# BatteryStepDownHV.net
KiCad netlist of a schematic drawn in Altium Designer
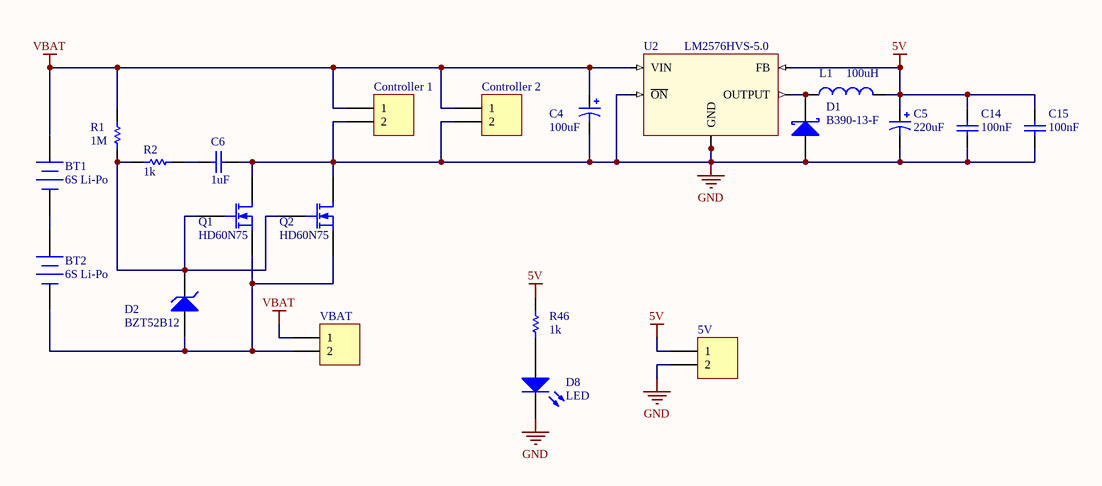
[diagram p0: BatteryStepDownHV.SchDoc]

(export (version "E")
  (design (tool "Eeschema 10.0.6"))
  (components
    (comp (ref "5V")
      (value "Header 2")
      (footprint "HDR1X2")
      (description "Header, 2-Pin")
      (fields (field (name "PUBLISHER") "Altium Limited"))
      (libsource (lib "Miscellaneous Connectors") (part "Header 2"))
    )
    (comp (ref "BT1")
      (value "6S Li-Po")
      (footprint "Wire Terminals")
      (description "Multicell Battery")
      (fields (field (name "PUBLISHER") "Altium Limited"))
      (libsource (lib "sumo") (part "Battery"))
    )
    (comp (ref "BT2")
      (value "6S Li-Po")
      (footprint "Wire Terminals")
      (description "Multicell Battery")
      (fields (field (name "PUBLISHER") "Altium Limited"))
      (libsource (lib "sumo") (part "Battery"))
    )
    (comp (ref "C4")
      (value "100uF")
      (footprint "10x10.5")
      (description "Polarized Capacitor (Radial)")
      (fields (field (name "Comment") "Cap Pol1") (field (name "PUBLISHER") "Altium Limited"))
      (libsource (lib "Miscellaneous Devices") (part "Cap Pol1"))
    )
    (comp (ref "C5")
      (value "220uF")
      (footprint "6.3X5.4")
      (description "Polarized Capacitor (Radial)")
      (fields (field (name "Comment") "Cap Pol1") (field (name "PUBLISHER") "Altium Limited"))
      (libsource (lib "Miscellaneous Devices") (part "Cap Pol1"))
    )
    (comp (ref "C6")
      (value "1uF")
      (footprint "6-0805_M")
      (description "Capacitor")
      (fields (field (name "Comment") "Cap") (field (name "PUBLISHER") "Altium Limited"))
      (libsource (lib "Miscellaneous Devices") (part "Cap"))
    )
    (comp (ref "C14")
      (value "100nF")
      (footprint "J1-0603")
      (description "Capacitor")
      (fields (field (name "Comment") "Cap") (field (name "PUBLISHER") "Altium Limited"))
      (libsource (lib "Miscellaneous Devices") (part "Cap"))
    )
    (comp (ref "C15")
      (value "100nF")
      (footprint "J1-0603")
      (description "Capacitor")
      (fields (field (name "Comment") "Cap") (field (name "PUBLISHER") "Altium Limited"))
      (libsource (lib "Miscellaneous Devices") (part "Cap"))
    )
    (comp (ref "Controller 1")
      (value "Header 2")
      (footprint "Wire Terminals")
      (description "Header, 2-Pin")
      (fields (field (name "PUBLISHER") "Altium Limited"))
      (libsource (lib "Miscellaneous Connectors") (part "Header 2"))
    )
    (comp (ref "Controller 2")
      (value "Header 2")
      (footprint "Wire Terminals")
      (description "Header, 2-Pin")
      (fields (field (name "PUBLISHER") "Altium Limited"))
      (libsource (lib "Miscellaneous Connectors") (part "Header 2"))
    )
    (comp (ref "D1")
      (value "B390-13-F")
      (footprint "B390")
      (description "Schottky Diode")
      (fields (field (name "PUBLISHER") "Altium Limited"))
      (libsource (lib "Miscellaneous Devices") (part "D Schottky"))
    )
    (comp (ref "D2")
      (value "BZT52B12")
      (footprint "SOD-123")
      (description "Zener Diode")
      (fields (field (name "PUBLISHER") "Altium Limited"))
      (libsource (lib "Miscellaneous Devices") (part "D Zener"))
    )
    (comp (ref "D8")
      (value "LED")
      (footprint "J1-0603 LED")
      (fields (field (name "PUBLISHER") "Altium Limited"))
      (libsource (lib "sumo") (part "LED"))
    )
    (comp (ref "L1")
      (value "100uH")
      (footprint "SLF12575")
      (description "Inductor")
      (fields (field (name "PUBLISHER") "Altium Limited"))
      (libsource (lib "Miscellaneous Devices") (part "Inductor"))
    )
    (comp (ref "Q1")
      (value "HD60N75")
      (footprint "TO-252")
      (description "N-Channel MOSFET 75V/60A")
      (fields (field (name "PUBLISHER") "Altium Limited"))
      (libsource (lib "sumo") (part "HD60N75"))
    )
    (comp (ref "Q2")
      (value "HD60N75")
      (footprint "TO-252")
      (description "N-Channel MOSFET 75V/60A")
      (fields (field (name "PUBLISHER") "Altium Limited"))
      (libsource (lib "sumo") (part "HD60N75"))
    )
    (comp (ref "R1")
      (value "1M")
      (footprint "J1-0603")
      (description "Resistor")
      (fields (field (name "Comment") "Res1") (field (name "PUBLISHER") "Altium Limited"))
      (libsource (lib "Miscellaneous Devices") (part "Res1"))
    )
    (comp (ref "R2")
      (value "1k")
      (footprint "J1-0603")
      (description "Resistor")
      (fields (field (name "Comment") "Res1") (field (name "PUBLISHER") "Altium Limited"))
      (libsource (lib "Miscellaneous Devices") (part "Res1"))
    )
    (comp (ref "R46")
      (value "1k")
      (footprint "J1-0603")
      (description "Resistor")
      (fields (field (name "Comment") "Res1") (field (name "PUBLISHER") "Altium Limited"))
      (libsource (lib "Miscellaneous Devices") (part "Res1"))
    )
    (comp (ref "U2")
      (value "LM2576HVS-5.0")
      (footprint "KTT0005B")
      (libsource (lib "sumo") (part "LM2576/HV"))
    )
    (comp (ref "VBAT")
      (value "Header 2")
      (footprint "HDR1X2")
      (description "Header, 2-Pin")
      (fields (field (name "PUBLISHER") "Altium Limited"))
      (libsource (lib "Miscellaneous Connectors") (part "Header 2"))
    )
  )
  (nets
    (net (code "1") (name "5V") (class "Default")
      (node (ref "5V") (pin "1") (pinfunction "1_1") (pintype "passive"))
      (node (ref "C14") (pin "2") (pinfunction "2_2") (pintype "passive"))
      (node (ref "C15") (pin "2") (pinfunction "2_2") (pintype "passive"))
      (node (ref "C5") (pin "1") (pinfunction "1_1") (pintype "passive"))
      (node (ref "L1") (pin "2") (pinfunction "2_2") (pintype "passive"))
      (node (ref "R46") (pin "2") (pinfunction "2_2") (pintype "passive"))
      (node (ref "U2") (pin "4") (pinfunction "FB_4") (pintype "input"))
    )
    (net (code "2") (name "GND") (class "Default")
      (node (ref "5V") (pin "2") (pinfunction "2_2") (pintype "passive"))
      (node (ref "C14") (pin "1") (pinfunction "1_1") (pintype "passive"))
      (node (ref "C15") (pin "1") (pinfunction "1_1") (pintype "passive"))
      (node (ref "C4") (pin "2") (pinfunction "2_2") (pintype "passive"))
      (node (ref "C5") (pin "2") (pinfunction "2_2") (pintype "passive"))
      (node (ref "C6") (pin "1") (pinfunction "1_1") (pintype "passive"))
      (node (ref "Controller 1") (pin "2") (pinfunction "2_2") (pintype "passive"))
      (node (ref "Controller 2") (pin "2") (pinfunction "2_2") (pintype "passive"))
      (node (ref "D1") (pin "1") (pinfunction "A_1") (pintype "passive"))
      (node (ref "D8") (pin "2") (pinfunction "K_2") (pintype "passive"))
      (node (ref "Q1") (pin "2") (pinfunction "D_2") (pintype "passive"))
      (node (ref "Q2") (pin "2") (pinfunction "D_2") (pintype "passive"))
      (node (ref "U2") (pin "3") (pinfunction "GND_3") (pintype "power_in"))
      (node (ref "U2") (pin "5") (pinfunction "~{ON}_5") (pintype "input"))
      (node (ref "U2") (pin "6") (pinfunction "TAB_6") (pintype "power_in"))
    )
    (net (code "3") (name "Net-(BT1--)") (class "Default")
      (node (ref "BT1") (pin "2") (pinfunction "-_2") (pintype "passive"))
      (node (ref "BT2") (pin "1") (pinfunction "+_1") (pintype "passive"))
    )
    (net (code "4") (name "Net-(BT2--)") (class "Default")
      (node (ref "BT2") (pin "2") (pinfunction "-_2") (pintype "passive"))
      (node (ref "D2") (pin "1") (pinfunction "A_1") (pintype "passive"))
      (node (ref "Q1") (pin "3") (pinfunction "S_3") (pintype "passive"))
      (node (ref "Q2") (pin "3") (pinfunction "S_3") (pintype "passive"))
      (node (ref "VBAT") (pin "2") (pinfunction "2_2") (pintype "passive"))
    )
    (net (code "5") (name "Net-(C6-Pad2)") (class "Default")
      (node (ref "C6") (pin "2") (pinfunction "2_2") (pintype "passive"))
      (node (ref "R2") (pin "2") (pinfunction "2_2") (pintype "passive"))
    )
    (net (code "6") (name "Net-(D1-K)") (class "Default")
      (node (ref "D1") (pin "2") (pinfunction "K_2") (pintype "passive"))
      (node (ref "L1") (pin "1") (pinfunction "1_1") (pintype "passive"))
      (node (ref "U2") (pin "2") (pinfunction "OUTPUT_2") (pintype "output"))
    )
    (net (code "7") (name "Net-(D2-K)") (class "Default")
      (node (ref "D2") (pin "2") (pinfunction "K_2") (pintype "passive"))
      (node (ref "Q1") (pin "1") (pinfunction "G_1") (pintype "passive"))
      (node (ref "Q2") (pin "1") (pinfunction "G_1") (pintype "passive"))
      (node (ref "R1") (pin "1") (pinfunction "1_1") (pintype "passive"))
      (node (ref "R2") (pin "1") (pinfunction "1_1") (pintype "passive"))
    )
    (net (code "8") (name "Net-(D8-A)") (class "Default")
      (node (ref "D8") (pin "1") (pinfunction "A_1") (pintype "passive"))
      (node (ref "R46") (pin "1") (pinfunction "1_1") (pintype "passive"))
    )
    (net (code "9") (name "VBAT") (class "Default")
      (node (ref "BT1") (pin "1") (pinfunction "+_1") (pintype "passive"))
      (node (ref "C4") (pin "1") (pinfunction "1_1") (pintype "passive"))
      (node (ref "Controller 1") (pin "1") (pinfunction "1_1") (pintype "passive"))
      (node (ref "Controller 2") (pin "1") (pinfunction "1_1") (pintype "passive"))
      (node (ref "R1") (pin "2") (pinfunction "2_2") (pintype "passive"))
      (node (ref "U2") (pin "1") (pinfunction "VIN_1") (pintype "input"))
      (node (ref "VBAT") (pin "1") (pinfunction "1_1") (pintype "passive"))
    )
  )
)
